# VISUR-botI_b.net
KiCad netlist of a schematic drawn in Altium Designer
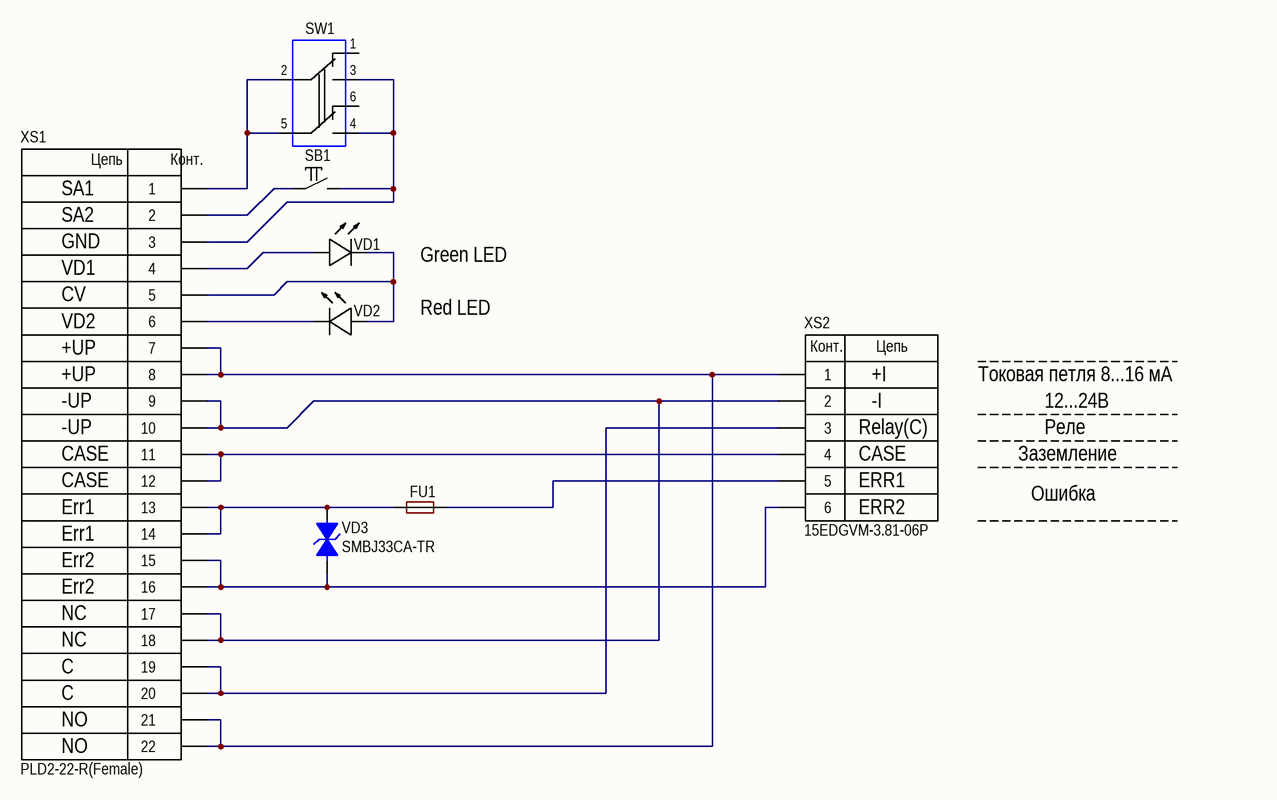
[diagram p0: VISUR-botI_b.SchDoc]

(export (version "E")
  (design (tool "Eeschema 10.0.6"))
  (components
    (comp (ref "FU1")
      (value "~")
      (footprint "FUSE: 1812")
      (fields
        (field (name "MANUFACTURER") "Littelfuse")
        (field (name "VALUEMANUFACTURERPARTNUMBER") "Electromechanics relay, 250VAC, , 5x20mm, ")
        (field (name "PARTNUMBER") "01110501Z")
      )
      (libsource (lib "electromechanics") (part "Fuse"))
    )
    (comp (ref "SB1")
      (value "~")
      (footprint "BUT: 6x6")
      (fields
        (field (name "MANUFACTURER") "TE Connectivity")
        (field (name "VALUEMANUFACTURERPARTNUMBER") "Tactile button, 6x6mm")
        (field (name "PARTNUMBER") "FSM2JSMAATR")
      )
      (libsource (lib "electromechanics") (part "Button_tactile"))
    )
    (comp (ref "SW1")
      (value "JS202011SCQN")
      (footprint "JS202011CQN")
      (description "Переключатель")
      (fields
        (field (name "MANUFACTURER") "C&K Component")
        (field (name "REPLACEMENTPART1PARTNUMBER") "is-1390")
      )
      (libsource (lib "Switch") (part "JS202011SCQN"))
    )
    (comp (ref "VD1")
      (value "KM2520SURCK09")
      (footprint "KM2520SURCK09")
      (description "LED")
      (libsource (lib "Kingbright LED") (part "KM2520SURCK09"))
    )
    (comp (ref "VD2")
      (value "KM2520SURCK09")
      (footprint "KM2520SURCK09")
      (description "LED")
      (libsource (lib "Kingbright LED") (part "KM2520SURCK09"))
    )
    (comp (ref "VD3")
      (value "SMBJ33CA-TR")
      (footprint "DIODE: SMB")
      (libsource (lib "diode") (part "SMBJ10CA-TR"))
    )
    (comp (ref "XS1")
      (value "PLD2-22-R(Female)")
      (footprint "CON: PLD2-22-R(Female)")
      (libsource (lib "connector") (part "PLD2-22(Female)"))
    )
    (comp (ref "XS2")
      (value "15EDGVM-3.81-06P")
      (footprint "CON: 15EDGVM-3.81-06P")
      (libsource (lib "connector") (part "15EDGVM-3.81-06P"))
    )
  )
  (nets
    (net (code "1") (name "Net-(FU1-Pad1)") (class "Default")
      (node (ref "FU1") (pin "1") (pinfunction "1_1") (pintype "passive"))
      (node (ref "VD3") (pin "2") (pinfunction "2_2") (pintype "passive"))
      (node (ref "XS1") (pin "13") (pinfunction "13_13") (pintype "power_in"))
      (node (ref "XS1") (pin "14") (pinfunction "14_14") (pintype "power_in"))
    )
    (net (code "2") (name "Net-(FU1-Pad2)") (class "Default")
      (node (ref "FU1") (pin "2") (pinfunction "2_2") (pintype "passive"))
      (node (ref "XS2") (pin "5") (pinfunction "5_5") (pintype "passive"))
    )
    (net (code "3") (name "Net-(SB1-Pad1)") (class "Default")
      (node (ref "SB1") (pin "1") (pinfunction "1_1") (pintype "passive"))
      (node (ref "XS1") (pin "2") (pinfunction "2_2") (pintype "passive"))
    )
    (net (code "4") (name "Net-(SB1-Pad2)") (class "Default")
      (node (ref "SB1") (pin "2") (pinfunction "2_2") (pintype "passive"))
      (node (ref "SW1") (pin "3") (pinfunction "3_3") (pintype "passive"))
      (node (ref "SW1") (pin "4") (pinfunction "4_4") (pintype "passive"))
      (node (ref "XS1") (pin "3") (pinfunction "3_3") (pintype "power_in"))
    )
    (net (code "5") (name "Net-(SW1-Pad2)") (class "Default")
      (node (ref "SW1") (pin "2") (pinfunction "2_2") (pintype "passive"))
      (node (ref "SW1") (pin "5") (pinfunction "5_5") (pintype "passive"))
      (node (ref "XS1") (pin "1") (pinfunction "1_1") (pintype "passive"))
    )
    (net (code "6") (name "Net-(VD1-A)") (class "Default")
      (node (ref "VD1") (pin "1") (pinfunction "A_1") (pintype "passive"))
      (node (ref "XS1") (pin "4") (pinfunction "4_4") (pintype "power_in"))
    )
    (net (code "7") (name "Net-(VD1-K)") (class "Default")
      (node (ref "VD1") (pin "2") (pinfunction "K_2") (pintype "passive"))
      (node (ref "VD2") (pin "1") (pinfunction "A_1") (pintype "passive"))
      (node (ref "XS1") (pin "5") (pinfunction "5_5") (pintype "power_in"))
    )
    (net (code "8") (name "Net-(VD2-K)") (class "Default")
      (node (ref "VD2") (pin "2") (pinfunction "K_2") (pintype "passive"))
      (node (ref "XS1") (pin "6") (pinfunction "6_6") (pintype "power_in"))
    )
    (net (code "9") (name "Net-(VD3-Pad1)") (class "Default")
      (node (ref "VD3") (pin "1") (pinfunction "1_1") (pintype "passive"))
      (node (ref "XS1") (pin "15") (pinfunction "15_15") (pintype "passive"))
      (node (ref "XS1") (pin "16") (pinfunction "16_16") (pintype "passive"))
      (node (ref "XS2") (pin "6") (pinfunction "6_6") (pintype "passive"))
    )
    (net (code "10") (name "Net-(XS1-Pad10)") (class "Default")
      (node (ref "XS1") (pin "10") (pinfunction "10_10") (pintype "power_in"))
      (node (ref "XS1") (pin "17") (pinfunction "17_17") (pintype "passive"))
      (node (ref "XS1") (pin "18") (pinfunction "18_18") (pintype "passive"))
      (node (ref "XS1") (pin "9") (pinfunction "9_9") (pintype "power_in"))
      (node (ref "XS2") (pin "2") (pinfunction "2_2") (pintype "passive"))
    )
    (net (code "11") (name "Net-(XS1-Pad11)") (class "Default")
      (node (ref "XS1") (pin "11") (pinfunction "11_11") (pintype "power_in"))
      (node (ref "XS1") (pin "12") (pinfunction "12_12") (pintype "power_in"))
      (node (ref "XS2") (pin "4") (pinfunction "4_4") (pintype "passive"))
    )
    (net (code "12") (name "Net-(XS1-Pad19)") (class "Default")
      (node (ref "XS1") (pin "19") (pinfunction "19_19") (pintype "passive"))
      (node (ref "XS1") (pin "20") (pinfunction "20_20") (pintype "passive"))
      (node (ref "XS2") (pin "3") (pinfunction "3_3") (pintype "passive"))
    )
    (net (code "13") (name "Net-(XS1-Pad21)") (class "Default")
      (node (ref "XS1") (pin "21") (pinfunction "21_21") (pintype "passive"))
      (node (ref "XS1") (pin "22") (pinfunction "22_22") (pintype "passive"))
      (node (ref "XS1") (pin "7") (pinfunction "7_7") (pintype "power_in"))
      (node (ref "XS1") (pin "8") (pinfunction "8_8") (pintype "power_in"))
      (node (ref "XS2") (pin "1") (pinfunction "1_1") (pintype "passive"))
    )
    (net (code "14") (name "unconnected-(SW1-Pad1)") (class "Default")
      (node (ref "SW1") (pin "1") (pinfunction "1_1") (pintype "passive"))
    )
    (net (code "15") (name "unconnected-(SW1-Pad6)") (class "Default")
      (node (ref "SW1") (pin "6") (pinfunction "6_6") (pintype "passive"))
    )
  )
)
